# ST_LINK_V2-1.net
KiCad netlist of a schematic drawn in Altium Designer
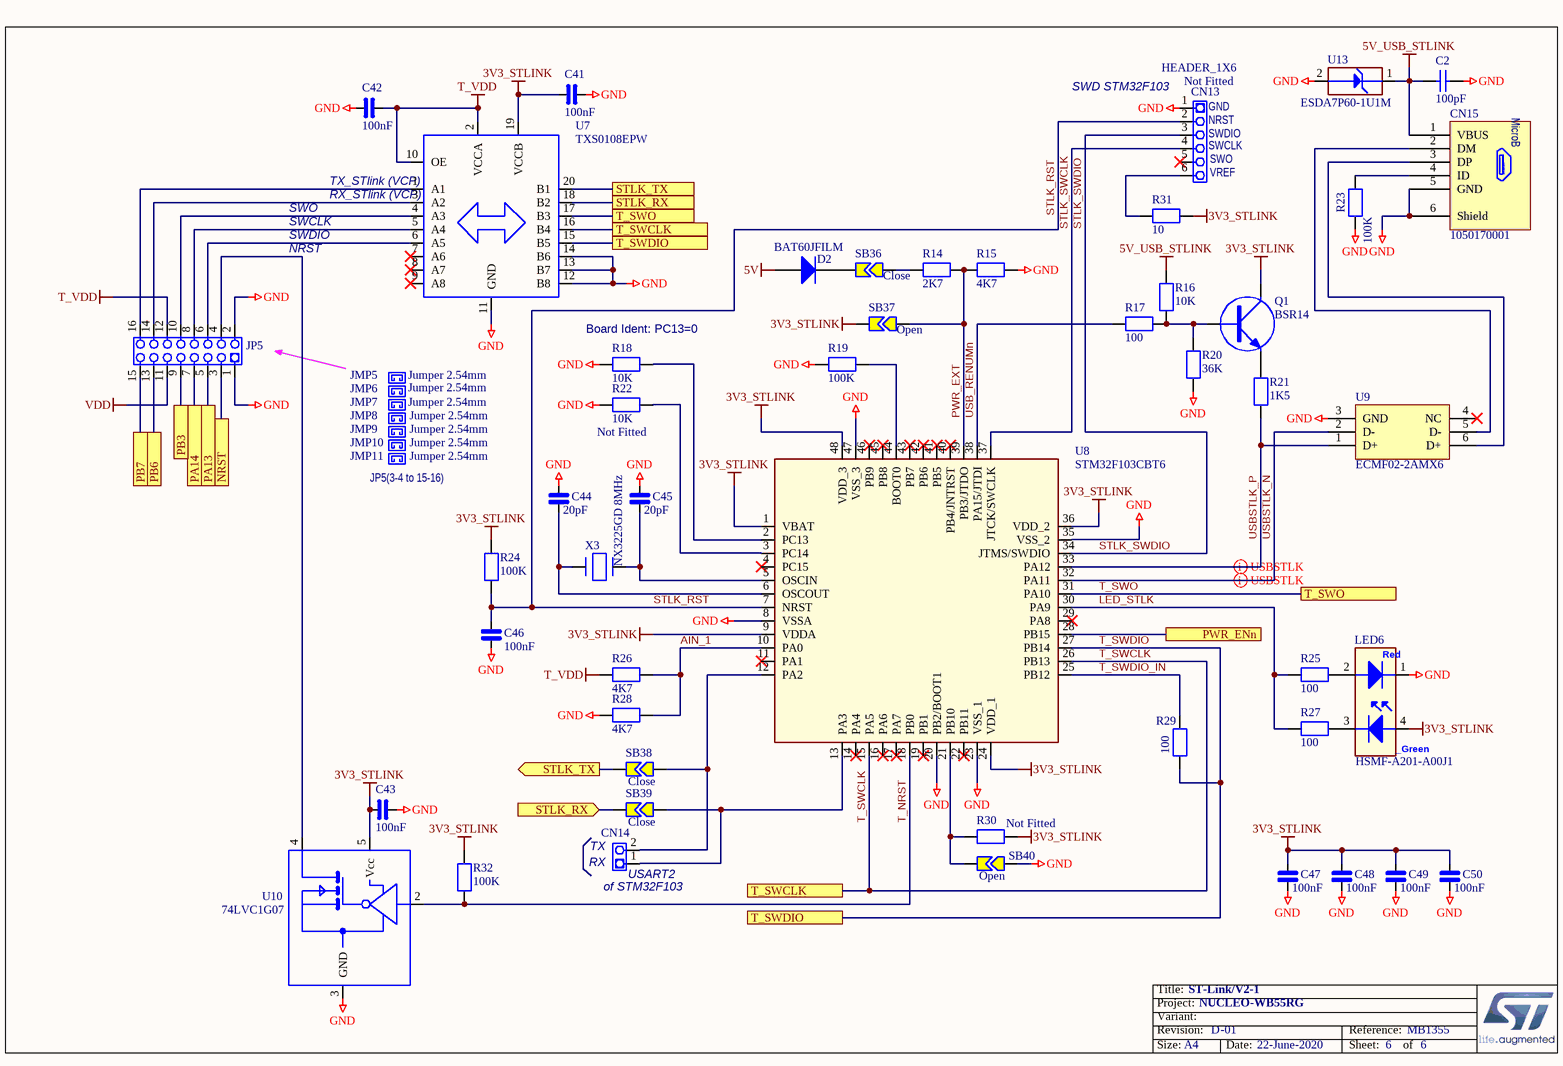
[diagram p0: ST_LINK_V2-1.SCHDOC]

(export (version "E")
  (design (tool "Eeschema 10.0.6"))
  (components
    (comp (ref "C2")
      (value "100pF")
      (footprint "C0402")
      (description "Capacitor, MLCC, 100pF, 50V, NPO, 5%, 0402, T=0,5mm")
      (fields
        (field (name "INTERNAL_PART_NUMBER") "MCD-00205")
        (field (name "MANUFACTURER_PART_NUMBER") "CC0402JRNPO9BN101")
        (field (name "PROVIDED_BY") "SUBCO")
      )
      (libsource (lib "MCD_PARTS_database") (part "Capacitor"))
    )
    (comp (ref "C41")
      (value "100nF")
      (footprint "0402_CAP_NPOL")
      (description "Capacitor_not polarized")
      (libsource (lib "ST_Lib3D") (part "CAP_NPOL"))
    )
    (comp (ref "C42")
      (value "100nF")
      (footprint "0402_CAP_NPOL")
      (description "Capacitor_not polarized")
      (libsource (lib "ST_Lib3D") (part "CAP_NPOL"))
    )
    (comp (ref "C43")
      (value "100nF")
      (footprint "0402_CAP_NPOL")
      (description "Capacitor_not polarized")
      (libsource (lib "ST_Lib3D") (part "CAP_NPOL"))
    )
    (comp (ref "C44")
      (value "20pF")
      (footprint "0402_CAP_NPOL")
      (description "Capacitor_not polarized")
      (libsource (lib "ST_Lib3D") (part "CAP_NPOL"))
    )
    (comp (ref "C45")
      (value "20pF")
      (footprint "0402_CAP_NPOL")
      (description "Capacitor_not polarized")
      (libsource (lib "ST_Lib3D") (part "CAP_NPOL"))
    )
    (comp (ref "C46")
      (value "100nF")
      (footprint "0402_CAP_NPOL")
      (description "Capacitor_not polarized")
      (libsource (lib "ST_Lib3D") (part "CAP_NPOL"))
    )
    (comp (ref "C47")
      (value "100nF")
      (footprint "0402_CAP_NPOL")
      (description "Capacitor_not polarized")
      (libsource (lib "ST_Lib3D") (part "CAP_NPOL"))
    )
    (comp (ref "C48")
      (value "100nF")
      (footprint "0402_CAP_NPOL")
      (description "Capacitor_not polarized")
      (libsource (lib "ST_Lib3D") (part "CAP_NPOL"))
    )
    (comp (ref "C49")
      (value "100nF")
      (footprint "0402_CAP_NPOL")
      (description "Capacitor_not polarized")
      (libsource (lib "ST_Lib3D") (part "CAP_NPOL"))
    )
    (comp (ref "C50")
      (value "100nF")
      (footprint "0402_CAP_NPOL")
      (description "Capacitor_not polarized")
      (libsource (lib "ST_Lib3D") (part "CAP_NPOL"))
    )
    (comp (ref "CN13")
      (value "HEADER_1X6")
      (footprint "Header NF 1x6x2.54 TH")
      (fields (field (name "FITTED") "Not Fitted"))
      (libsource (lib "Connector") (part "HEADER_1X6"))
    )
    (comp (ref "CN14")
      (value "HEADER_1X2")
      (footprint "Header NF 1x2x2.54 TH")
      (libsource (lib "Connector") (part "HEADER_1X2"))
    )
    (comp (ref "CN15")
      (value "1050170001")
      (footprint "USBMICROB_MOLEX_105017-0001_H2P90")
      (description "USB-MICRO-B, 1050170001, SMT, MOLEX")
      (libsource (lib "Connector") (part "1050170001"))
    )
    (comp (ref "D2")
      (value "BAT60JFILM")
      (footprint "SOD-323")
      (description "Default Diode")
      (fields (field (name "PUBLISHER") "Altium Limited"))
      (libsource (lib "MB1144_1") (part "Diode"))
    )
    (comp (ref "JMP5")
      (value "Jumper 2.54mm")
      (footprint "Jumper 2.54mm BLACK")
      (libsource (lib "Connector") (part "Jumper 2.54mm"))
    )
    (comp (ref "JMP6")
      (value "Jumper 2.54mm")
      (footprint "Jumper 2.54mm BLACK")
      (libsource (lib "Connector") (part "Jumper 2.54mm"))
    )
    (comp (ref "JMP7")
      (value "Jumper 2.54mm")
      (footprint "Jumper 2.54mm BLACK")
      (libsource (lib "Connector") (part "Jumper 2.54mm"))
    )
    (comp (ref "JMP8")
      (value "Jumper 2.54mm")
      (footprint "Jumper 2.54mm BLACK")
      (libsource (lib "Connector") (part "Jumper 2.54mm"))
    )
    (comp (ref "JMP9")
      (value "Jumper 2.54mm")
      (footprint "Jumper 2.54mm BLACK")
      (libsource (lib "Connector") (part "Jumper 2.54mm"))
    )
    (comp (ref "JMP10")
      (value "Jumper 2.54mm")
      (footprint "Jumper 2.54mm BLACK")
      (libsource (lib "Connector") (part "Jumper 2.54mm"))
    )
    (comp (ref "JMP11")
      (value "Jumper 2.54mm")
      (footprint "Jumper 2.54mm BLACK")
      (libsource (lib "Connector") (part "Jumper 2.54mm"))
    )
    (comp (ref "JP5")
      (value "HEADER_2X8")
      (footprint "Header M 2x8x2.54 TH V")
      (libsource (lib "Connector") (part "HEADER_2X8"))
    )
    (comp (ref "LED6")
      (value "HSMF-A201-A00J1")
      (footprint "HSMF-A201")
      (description "Bicolor Led")
      (libsource (lib "MB1136") (part "LD_BICOLOR_CMS"))
    )
    (comp (ref "Q1")
      (value "BSR14")
      (footprint "SOT23-3")
      (description "2N2222_SOT23")
      (libsource (lib "Active") (part "2N2222"))
    )
    (comp (ref "R14")
      (value "2K7")
      (footprint "0402_RES")
      (description "Resistor")
      (libsource (lib "Lib3D_Altium10_Schlib") (part "RES"))
    )
    (comp (ref "R15")
      (value "4K7")
      (footprint "0402_RES")
      (description "Resistor")
      (libsource (lib "Lib3D_Altium10_Schlib") (part "RES"))
    )
    (comp (ref "R16")
      (value "10K")
      (footprint "0402_RES")
      (description "Resistor")
      (libsource (lib "Lib3D_Altium10_Schlib") (part "RES"))
    )
    (comp (ref "R17")
      (value "100")
      (footprint "0402_RES")
      (description "Resistor")
      (libsource (lib "Lib3D_Altium10_Schlib") (part "RES"))
    )
    (comp (ref "R18")
      (value "10K")
      (footprint "0402_RES")
      (description "Resistor")
      (libsource (lib "Lib3D_Altium10_Schlib") (part "RES"))
    )
    (comp (ref "R19")
      (value "100K")
      (footprint "0402_RES")
      (description "Resistor")
      (libsource (lib "Lib3D_Altium10_Schlib") (part "RES"))
    )
    (comp (ref "R20")
      (value "36K")
      (footprint "0402_RES")
      (description "Resistor")
      (libsource (lib "Lib3D_Altium10_Schlib") (part "RES"))
    )
    (comp (ref "R21")
      (value "1K5")
      (footprint "0402_RES")
      (description "Resistor")
      (libsource (lib "Lib3D_Altium10_Schlib") (part "RES"))
    )
    (comp (ref "R22")
      (value "10K")
      (footprint "0402_RES")
      (description "Resistor")
      (fields (field (name "FITTED") "Not Fitted"))
      (libsource (lib "Lib3D_Altium10_Schlib") (part "RES"))
    )
    (comp (ref "R23")
      (value "100K")
      (footprint "0402_RES")
      (description "Resistor")
      (libsource (lib "Lib3D_Altium10_Schlib") (part "RES"))
    )
    (comp (ref "R24")
      (value "100K")
      (footprint "0402_RES")
      (description "Resistor")
      (libsource (lib "Lib3D_Altium10_Schlib") (part "RES"))
    )
    (comp (ref "R25")
      (value "100")
      (footprint "0402_RES")
      (description "Resistor")
      (libsource (lib "Lib3D_Altium10_Schlib") (part "RES"))
    )
    (comp (ref "R26")
      (value "4K7")
      (footprint "0402_RES")
      (description "Resistor")
      (libsource (lib "Lib3D_Altium10_Schlib") (part "RES"))
    )
    (comp (ref "R27")
      (value "100")
      (footprint "0402_RES")
      (description "Resistor")
      (libsource (lib "Lib3D_Altium10_Schlib") (part "RES"))
    )
    (comp (ref "R28")
      (value "4K7")
      (footprint "0402_RES")
      (description "Resistor")
      (libsource (lib "Lib3D_Altium10_Schlib") (part "RES"))
    )
    (comp (ref "R29")
      (value "100")
      (footprint "0402_RES")
      (description "Resistor")
      (libsource (lib "Lib3D_Altium10_Schlib") (part "RES"))
    )
    (comp (ref "R30")
      (value "~")
      (footprint "0402_RES")
      (description "Resistor")
      (fields (field (name "FITTED") "Not Fitted"))
      (libsource (lib "Lib3D_Altium10_Schlib") (part "RES"))
    )
    (comp (ref "R31")
      (value "10")
      (footprint "0402_RES")
      (description "Resistor")
      (libsource (lib "Lib3D_Altium10_Schlib") (part "RES"))
    )
    (comp (ref "R32")
      (value "100K")
      (footprint "0402_RES")
      (description "Resistor")
      (libsource (lib "Lib3D_Altium10_Schlib") (part "RES"))
    )
    (comp (ref "SB36")
      (value "Close")
      (footprint "SB-tiny")
      (description "Solder Jumper")
      (fields (field (name "PUBLISHER") "Altium Limited"))
      (libsource (lib "Lib3D_Altium10_Schlib") (part "Strap2"))
    )
    (comp (ref "SB37")
      (value "Open")
      (footprint "SB-tiny")
      (description "Solder Jumper")
      (fields (field (name "PUBLISHER") "Altium Limited"))
      (libsource (lib "Lib3D_Altium10_Schlib") (part "Strap2"))
    )
    (comp (ref "SB38")
      (value "Close")
      (footprint "SB-tiny")
      (description "Solder Jumper")
      (fields (field (name "PUBLISHER") "Altium Limited"))
      (libsource (lib "Lib3D_Altium10_Schlib") (part "Strap2"))
    )
    (comp (ref "SB39")
      (value "Close")
      (footprint "SB-tiny")
      (description "Solder Jumper")
      (fields (field (name "PUBLISHER") "Altium Limited"))
      (libsource (lib "Lib3D_Altium10_Schlib") (part "Strap2"))
    )
    (comp (ref "SB40")
      (value "Open")
      (footprint "SB-tiny")
      (description "Solder Jumper")
      (fields (field (name "PUBLISHER") "Altium Limited"))
      (libsource (lib "Lib3D_Altium10_Schlib") (part "Strap2"))
    )
    (comp (ref "U7")
      (value "TXS0108EPW")
      (footprint "TSSOP20")
      (description "TXS0108E Bi-directional Level Shifter TSSOP20")
      (libsource (lib "Active") (part "TXS0108EPW"))
    )
    (comp (ref "U8")
      (value "STM32F103CBT6")
      (footprint "LQFP48_7X7_P050")
      (description "Medium-density performance line ARM-based 32-bit MCU with 128KB Flash")
      (libsource (lib "Active") (part "STM32F103CBT6"))
    )
    (comp (ref "U9")
      (value "ECMF02-2AMX6")
      (footprint "ESD_QFN-6L_1P7X1P5_P050")
      (description "Common mode filter with ESD protection for USB 2.0 interface")
      (fields
        (field (name "INTERNAL_PART_NUMBER") "MCD-00649")
        (field (name "MANUFACTURER") "STMICROELECTRONICS")
        (field (name "PROVIDED_BY") "SUBCO with ST control")
      )
      (libsource (lib "MCD_PARTS_database") (part "ECMF02-2AMX6"))
    )
    (comp (ref "U10")
      (value "74LVC1G07")
      (footprint "SOT353-1")
      (libsource (lib "ST_Lib3D") (part "74LVC1G07"))
    )
    (comp (ref "U13")
      (value "ESDA7P60-1U1M")
      (footprint "ESD_QFN2_1P6X1_P125")
      (description "High power transient voltage suppressor, 7V breakdown")
      (fields
        (field (name "INTERNAL_PART_NUMBER") "MCD-00251")
        (field (name "MANUFACTURER") "STMICROELECTRONICS")
        (field (name "PROVIDED_BY") "SUBCO with ST control")
      )
      (libsource (lib "MCD_PARTS_database") (part "ESD-TRANSIL"))
    )
    (comp (ref "X3")
      (value "NX3225GD 8MHz")
      (footprint "CRY_NX3225GD_2P")
      (description "Crystal 8MHz, 8pF, +-20ppm, 500ohms max,  SMD")
      (fields
        (field (name "INTERNAL_PART_NUMBER") "MCD-00092")
        (field (name "MANUFACTURER_PART_NUMBER") "NX3225GD 8MHz EXS00A-CG04874")
        (field (name "PROVIDED_BY") "SUBCO")
      )
      (libsource (lib "MCD_PARTS_database") (part "XTAL_2_PINS"))
    )
  )
  (nets
    (net (code "1") (name "/AIN_1") (class "Default")
      (node (ref "R26") (pin "1") (pinfunction "1_1") (pintype "passive"))
      (node (ref "R28") (pin "1") (pinfunction "1_1") (pintype "passive"))
      (node (ref "U8") (pin "10") (pinfunction "PA0_10") (pintype "passive"))
    )
    (net (code "2") (name "/LED_STLK") (class "Default")
      (node (ref "R25") (pin "2") (pinfunction "2_2") (pintype "passive"))
      (node (ref "R27") (pin "2") (pinfunction "2_2") (pintype "passive"))
      (node (ref "U8") (pin "30") (pinfunction "PA9_30") (pintype "passive"))
    )
    (net (code "3") (name "/NRST") (class "Default")
      (node (ref "JP5") (pin "3") (pinfunction "3_3") (pintype "passive"))
    )
    (net (code "4") (name "/PA13") (class "Default")
      (node (ref "JP5") (pin "5") (pinfunction "5_5") (pintype "passive"))
    )
    (net (code "5") (name "/PA14") (class "Default")
      (node (ref "JP5") (pin "7") (pinfunction "7_7") (pintype "passive"))
    )
    (net (code "6") (name "/PB3") (class "Default")
      (node (ref "JP5") (pin "9") (pinfunction "9_9") (pintype "passive"))
    )
    (net (code "7") (name "/PB6") (class "Default")
      (node (ref "JP5") (pin "13") (pinfunction "13_13") (pintype "passive"))
    )
    (net (code "8") (name "/PB7") (class "Default")
      (node (ref "JP5") (pin "15") (pinfunction "15_15") (pintype "passive"))
    )
    (net (code "9") (name "/PWR_ENn") (class "Default")
      (node (ref "U8") (pin "28") (pinfunction "PB15_28") (pintype "passive"))
    )
    (net (code "10") (name "/PWR_EXT") (class "Default")
      (node (ref "R14") (pin "2") (pinfunction "2_2") (pintype "passive"))
      (node (ref "R15") (pin "1") (pinfunction "1_1") (pintype "passive"))
      (node (ref "SB37") (pin "2") (pinfunction "2_2") (pintype "passive"))
      (node (ref "U8") (pin "39") (pinfunction "PB3/JTDO_39") (pintype "passive"))
    )
    (net (code "11") (name "/STLK_RST") (class "Default")
      (node (ref "C46") (pin "2") (pinfunction "2_2") (pintype "passive"))
      (node (ref "CN13") (pin "2") (pinfunction "2_2") (pintype "passive"))
      (node (ref "R24") (pin "1") (pinfunction "1_1") (pintype "passive"))
      (node (ref "U8") (pin "7") (pinfunction "NRST_7") (pintype "passive"))
    )
    (net (code "12") (name "/STLK_RX") (class "Default")
      (node (ref "SB39") (pin "1") (pinfunction "1_1") (pintype "passive"))
      (node (ref "U7") (pin "18") (pinfunction "B2_18") (pintype "passive"))
    )
    (net (code "13") (name "/STLK_SWCLK") (class "Default")
      (node (ref "CN13") (pin "4") (pinfunction "4_4") (pintype "passive"))
      (node (ref "U8") (pin "37") (pinfunction "JTCK/SWCLK_37") (pintype "passive"))
    )
    (net (code "14") (name "/STLK_SWDIO") (class "Default")
      (node (ref "CN13") (pin "3") (pinfunction "3_3") (pintype "passive"))
      (node (ref "U8") (pin "34") (pinfunction "JTMS/SWDIO_34") (pintype "passive"))
    )
    (net (code "15") (name "/STLK_TX") (class "Default")
      (node (ref "SB38") (pin "1") (pinfunction "1_1") (pintype "passive"))
      (node (ref "U7") (pin "20") (pinfunction "B1_20") (pintype "passive"))
    )
    (net (code "16") (name "/T_NRST") (class "Default")
      (node (ref "R32") (pin "1") (pinfunction "1_1") (pintype "passive"))
      (node (ref "U10") (pin "2") (pinfunction "A_2") (pintype "passive"))
      (node (ref "U8") (pin "18") (pinfunction "PB0_18") (pintype "passive"))
    )
    (net (code "17") (name "/T_SWCLK") (class "Default")
      (node (ref "U7") (pin "16") (pinfunction "B4_16") (pintype "passive"))
      (node (ref "U8") (pin "15") (pinfunction "PA5_15") (pintype "passive"))
      (node (ref "U8") (pin "26") (pinfunction "PB13_26") (pintype "passive"))
    )
    (net (code "18") (name "/T_SWDIO") (class "Default")
      (node (ref "R29") (pin "1") (pinfunction "1_1") (pintype "passive"))
      (node (ref "U7") (pin "15") (pinfunction "B5_15") (pintype "passive"))
      (node (ref "U8") (pin "27") (pinfunction "PB14_27") (pintype "passive"))
    )
    (net (code "19") (name "/T_SWDIO_IN") (class "Default")
      (node (ref "R29") (pin "2") (pinfunction "2_2") (pintype "passive"))
      (node (ref "U8") (pin "25") (pinfunction "PB12_25") (pintype "passive"))
    )
    (net (code "20") (name "/T_SWO") (class "Default")
      (node (ref "U7") (pin "17") (pinfunction "B3_17") (pintype "passive"))
      (node (ref "U8") (pin "31") (pinfunction "PA10_31") (pintype "passive"))
    )
    (net (code "21") (name "/USBSTLK_N") (class "Default")
      (node (ref "U8") (pin "32") (pinfunction "PA11_32") (pintype "passive"))
      (node (ref "U9") (pin "2") (pinfunction "D-_2") (pintype "passive"))
    )
    (net (code "22") (name "/USBSTLK_P") (class "Default")
      (node (ref "R21") (pin "1") (pinfunction "1_1") (pintype "passive"))
      (node (ref "U8") (pin "33") (pinfunction "PA12_33") (pintype "passive"))
      (node (ref "U9") (pin "1") (pinfunction "D+_1") (pintype "passive"))
    )
    (net (code "23") (name "/USB_RENUMn") (class "Default")
      (node (ref "R17") (pin "2") (pinfunction "2_2") (pintype "passive"))
      (node (ref "U8") (pin "38") (pinfunction "PA15/JTDI_38") (pintype "passive"))
    )
    (net (code "24") (name "3V3_STLINK") (class "Default")
      (node (ref "C41") (pin "1") (pinfunction "1_1") (pintype "passive"))
      (node (ref "C43") (pin "1") (pinfunction "1_1") (pintype "passive"))
      (node (ref "C47") (pin "1") (pinfunction "1_1") (pintype "passive"))
      (node (ref "C48") (pin "1") (pinfunction "1_1") (pintype "passive"))
      (node (ref "C49") (pin "1") (pinfunction "1_1") (pintype "passive"))
      (node (ref "C50") (pin "1") (pinfunction "1_1") (pintype "passive"))
      (node (ref "LED6") (pin "4") (pinfunction "4_4") (pintype "passive"))
      (node (ref "Q1") (pin "3") (pinfunction "C_3") (pintype "passive"))
      (node (ref "R24") (pin "2") (pinfunction "2_2") (pintype "passive"))
      (node (ref "R30") (pin "1") (pinfunction "1_1") (pintype "passive"))
      (node (ref "R31") (pin "2") (pinfunction "2_2") (pintype "passive"))
      (node (ref "R32") (pin "2") (pinfunction "2_2") (pintype "passive"))
      (node (ref "SB37") (pin "1") (pinfunction "1_1") (pintype "passive"))
      (node (ref "U10") (pin "5") (pinfunction "Vcc_5") (pintype "passive"))
      (node (ref "U7") (pin "19") (pinfunction "VCCB_19") (pintype "passive"))
      (node (ref "U8") (pin "1") (pinfunction "VBAT_1") (pintype "passive"))
      (node (ref "U8") (pin "24") (pinfunction "VDD_1_24") (pintype "passive"))
      (node (ref "U8") (pin "36") (pinfunction "VDD_2_36") (pintype "passive"))
      (node (ref "U8") (pin "48") (pinfunction "VDD_3_48") (pintype "passive"))
      (node (ref "U8") (pin "9") (pinfunction "VDDA_9") (pintype "passive"))
    )
    (net (code "25") (name "5V") (class "Default")
      (node (ref "D2") (pin "1") (pinfunction "A_1") (pintype "passive"))
    )
    (net (code "26") (name "5V_USB_STLINK") (class "Default")
      (node (ref "C2") (pin "1") (pinfunction "1_1") (pintype "passive"))
      (node (ref "CN15") (pin "1") (pinfunction "VBUS_1") (pintype "passive"))
      (node (ref "R16") (pin "2") (pinfunction "2_2") (pintype "passive"))
      (node (ref "U13") (pin "1") (pinfunction "IO1_1") (pintype "passive"))
    )
    (net (code "27") (name "GND") (class "Default")
      (node (ref "C2") (pin "2") (pinfunction "2_2") (pintype "passive"))
      (node (ref "C41") (pin "2") (pinfunction "2_2") (pintype "passive"))
      (node (ref "C42") (pin "1") (pinfunction "1_1") (pintype "passive"))
      (node (ref "C43") (pin "2") (pinfunction "2_2") (pintype "passive"))
      (node (ref "C44") (pin "1") (pinfunction "1_1") (pintype "passive"))
      (node (ref "C45") (pin "1") (pinfunction "1_1") (pintype "passive"))
      (node (ref "C46") (pin "1") (pinfunction "1_1") (pintype "passive"))
      (node (ref "C47") (pin "2") (pinfunction "2_2") (pintype "passive"))
      (node (ref "C48") (pin "2") (pinfunction "2_2") (pintype "passive"))
      (node (ref "C49") (pin "2") (pinfunction "2_2") (pintype "passive"))
      (node (ref "C50") (pin "2") (pinfunction "2_2") (pintype "passive"))
      (node (ref "CN13") (pin "1") (pinfunction "1_1") (pintype "passive"))
      (node (ref "CN15") (pin "5") (pinfunction "GND_5") (pintype "passive"))
      (node (ref "CN15") (pin "6") (pinfunction "Shield_6") (pintype "passive"))
      (node (ref "JP5") (pin "1") (pinfunction "1_1") (pintype "passive"))
      (node (ref "JP5") (pin "2") (pinfunction "2_2") (pintype "passive"))
      (node (ref "LED6") (pin "1") (pinfunction "1_1") (pintype "passive"))
      (node (ref "R15") (pin "2") (pinfunction "2_2") (pintype "passive"))
      (node (ref "R18") (pin "2") (pinfunction "2_2") (pintype "passive"))
      (node (ref "R19") (pin "1") (pinfunction "1_1") (pintype "passive"))
      (node (ref "R20") (pin "1") (pinfunction "1_1") (pintype "passive"))
      (node (ref "R22") (pin "2") (pinfunction "2_2") (pintype "passive"))
      (node (ref "R23") (pin "1") (pinfunction "1_1") (pintype "passive"))
      (node (ref "R28") (pin "2") (pinfunction "2_2") (pintype "passive"))
      (node (ref "SB40") (pin "2") (pinfunction "2_2") (pintype "passive"))
      (node (ref "U10") (pin "3") (pinfunction "GND_3") (pintype "passive"))
      (node (ref "U13") (pin "2") (pinfunction "GND_2") (pintype "passive"))
      (node (ref "U7") (pin "11") (pinfunction "GND_11") (pintype "passive"))
      (node (ref "U7") (pin "12") (pinfunction "B8_12") (pintype "passive"))
      (node (ref "U7") (pin "13") (pinfunction "B7_13") (pintype "passive"))
      (node (ref "U7") (pin "14") (pinfunction "B6_14") (pintype "passive"))
      (node (ref "U8") (pin "20") (pinfunction "PB2/BOOT1_20") (pintype "passive"))
      (node (ref "U8") (pin "23") (pinfunction "VSS_1_23") (pintype "passive"))
      (node (ref "U8") (pin "35") (pinfunction "VSS_2_35") (pintype "passive"))
      (node (ref "U8") (pin "47") (pinfunction "VSS_3_47") (pintype "passive"))
      (node (ref "U8") (pin "8") (pinfunction "VSSA_8") (pintype "passive"))
      (node (ref "U9") (pin "3") (pinfunction "GND_3") (pintype "passive"))
    )
    (net (code "28") (name "Net-(CN13-Pad6)") (class "Default")
      (node (ref "CN13") (pin "6") (pinfunction "6_6") (pintype "passive"))
      (node (ref "R31") (pin "1") (pinfunction "1_1") (pintype "passive"))
    )
    (net (code "29") (name "Net-(CN15-DM)") (class "Default")
      (node (ref "CN15") (pin "2") (pinfunction "DM_2") (pintype "passive"))
      (node (ref "U9") (pin "5") (pinfunction "D-_5") (pintype "passive"))
    )
    (net (code "30") (name "Net-(CN15-DP)") (class "Default")
      (node (ref "CN15") (pin "3") (pinfunction "DP_3") (pintype "passive"))
      (node (ref "U9") (pin "6") (pinfunction "D+_6") (pintype "passive"))
    )
    (net (code "31") (name "Net-(CN15-ID)") (class "Default")
      (node (ref "CN15") (pin "4") (pinfunction "ID_4") (pintype "passive"))
      (node (ref "R23") (pin "2") (pinfunction "2_2") (pintype "passive"))
    )
    (net (code "32") (name "Net-(D2-K)") (class "Default")
      (node (ref "D2") (pin "2") (pinfunction "K_2") (pintype "passive"))
      (node (ref "SB36") (pin "1") (pinfunction "1_1") (pintype "passive"))
    )
    (net (code "33") (name "Net-(LED6-Pad2)") (class "Default")
      (node (ref "LED6") (pin "2") (pinfunction "2_2") (pintype "passive"))
      (node (ref "R25") (pin "1") (pinfunction "1_1") (pintype "passive"))
    )
    (net (code "34") (name "Net-(LED6-Pad3)") (class "Default")
      (node (ref "LED6") (pin "3") (pinfunction "3_3") (pintype "passive"))
      (node (ref "R27") (pin "1") (pinfunction "1_1") (pintype "passive"))
    )
    (net (code "35") (name "Net-(Q1-B)") (class "Default")
      (node (ref "Q1") (pin "1") (pinfunction "B_1") (pintype "passive"))
      (node (ref "R16") (pin "1") (pinfunction "1_1") (pintype "passive"))
      (node (ref "R17") (pin "1") (pinfunction "1_1") (pintype "passive"))
      (node (ref "R20") (pin "2") (pinfunction "2_2") (pintype "passive"))
    )
    (net (code "36") (name "Net-(Q1-E)") (class "Default")
      (node (ref "Q1") (pin "2") (pinfunction "E_2") (pintype "passive"))
      (node (ref "R21") (pin "2") (pinfunction "2_2") (pintype "passive"))
    )
    (net (code "37") (name "Net-(R14-Pad1)") (class "Default")
      (node (ref "R14") (pin "1") (pinfunction "1_1") (pintype "passive"))
      (node (ref "SB36") (pin "2") (pinfunction "2_2") (pintype "passive"))
    )
    (net (code "38") (name "Net-(U7-A1)") (class "Default")
      (node (ref "JP5") (pin "16") (pinfunction "16_16") (pintype "passive"))
      (node (ref "U7") (pin "1") (pinfunction "A1_1") (pintype "passive"))
    )
    (net (code "39") (name "Net-(U7-A2)") (class "Default")
      (node (ref "JP5") (pin "14") (pinfunction "14_14") (pintype "passive"))
      (node (ref "U7") (pin "3") (pinfunction "A2_3") (pintype "passive"))
    )
    (net (code "40") (name "Net-(U7-A3)") (class "Default")
      (node (ref "JP5") (pin "10") (pinfunction "10_10") (pintype "passive"))
      (node (ref "U7") (pin "4") (pinfunction "A3_4") (pintype "passive"))
    )
    (net (code "41") (name "Net-(U7-A4)") (class "Default")
      (node (ref "JP5") (pin "8") (pinfunction "8_8") (pintype "passive"))
      (node (ref "U7") (pin "5") (pinfunction "A4_5") (pintype "passive"))
    )
    (net (code "42") (name "Net-(U7-A5)") (class "Default")
      (node (ref "JP5") (pin "6") (pinfunction "6_6") (pintype "passive"))
      (node (ref "U7") (pin "6") (pinfunction "A5_6") (pintype "passive"))
    )
    (net (code "43") (name "Net-(U8-BOOT0)") (class "Default")
      (node (ref "R19") (pin "2") (pinfunction "2_2") (pintype "passive"))
      (node (ref "U8") (pin "44") (pinfunction "BOOT0_44") (pintype "passive"))
    )
    (net (code "44") (name "Net-(U8-OSCIN)") (class "Default")
      (node (ref "C45") (pin "2") (pinfunction "2_2") (pintype "passive"))
      (node (ref "U8") (pin "5") (pinfunction "OSCIN_5") (pintype "passive"))
      (node (ref "X3") (pin "1") (pinfunction "X1_1") (pintype "passive"))
    )
    (net (code "45") (name "Net-(U8-OSCOUT)") (class "Default")
      (node (ref "C44") (pin "2") (pinfunction "2_2") (pintype "passive"))
      (node (ref "U8") (pin "6") (pinfunction "OSCOUT_6") (pintype "passive"))
      (node (ref "X3") (pin "2") (pinfunction "X2_2") (pintype "passive"))
    )
    (net (code "46") (name "Net-(U8-PA2)") (class "Default")
      (node (ref "CN14") (pin "2") (pinfunction "2_2") (pintype "passive"))
      (node (ref "SB38") (pin "2") (pinfunction "2_2") (pintype "passive"))
      (node (ref "U8") (pin "12") (pinfunction "PA2_12") (pintype "passive"))
    )
    (net (code "47") (name "Net-(U8-PA3)") (class "Default")
      (node (ref "CN14") (pin "1") (pinfunction "1_1") (pintype "passive"))
      (node (ref "SB39") (pin "2") (pinfunction "2_2") (pintype "passive"))
      (node (ref "U8") (pin "13") (pinfunction "PA3_13") (pintype "passive"))
    )
    (net (code "48") (name "Net-(U8-PB10)") (class "Default")
      (node (ref "R30") (pin "2") (pinfunction "2_2") (pintype "passive"))
      (node (ref "SB40") (pin "1") (pinfunction "1_1") (pintype "passive"))
      (node (ref "U8") (pin "21") (pinfunction "PB10_21") (pintype "passive"))
    )
    (net (code "49") (name "Net-(U8-PC13)") (class "Default")
      (node (ref "R18") (pin "1") (pinfunction "1_1") (pintype "passive"))
      (node (ref "U8") (pin "2") (pinfunction "PC13_2") (pintype "passive"))
    )
    (net (code "50") (name "Net-(U8-PC14)") (class "Default")
      (node (ref "R22") (pin "1") (pinfunction "1_1") (pintype "passive"))
      (node (ref "U8") (pin "3") (pinfunction "PC14_3") (pintype "passive"))
    )
    (net (code "51") (name "Net-(U10-Y)") (class "Default")
      (node (ref "JP5") (pin "4") (pinfunction "4_4") (pintype "passive"))
      (node (ref "U10") (pin "4") (pinfunction "Y_4") (pintype "passive"))
    )
    (net (code "52") (name "T_VDD") (class "Default")
      (node (ref "C42") (pin "2") (pinfunction "2_2") (pintype "passive"))
      (node (ref "JP5") (pin "12") (pinfunction "12_12") (pintype "passive"))
      (node (ref "R26") (pin "2") (pinfunction "2_2") (pintype "passive"))
      (node (ref "U7") (pin "10") (pinfunction "OE_10") (pintype "passive"))
      (node (ref "U7") (pin "2") (pinfunction "VCCA_2") (pintype "passive"))
    )
    (net (code "53") (name "VDD") (class "Default")
      (node (ref "JP5") (pin "11") (pinfunction "11_11") (pintype "passive"))
    )
    (net (code "54") (name "unconnected-(CN13-Pad5)") (class "Default")
      (node (ref "CN13") (pin "5") (pinfunction "5_5") (pintype "passive+no_connect"))
    )
    (net (code "55") (name "unconnected-(U7-A6-Pad7)") (class "Default")
      (node (ref "U7") (pin "7") (pinfunction "A6_7") (pintype "passive+no_connect"))
    )
    (net (code "56") (name "unconnected-(U7-A7-Pad8)") (class "Default")
      (node (ref "U7") (pin "8") (pinfunction "A7_8") (pintype "passive+no_connect"))
    )
    (net (code "57") (name "unconnected-(U7-A8-Pad9)") (class "Default")
      (node (ref "U7") (pin "9") (pinfunction "A8_9") (pintype "passive+no_connect"))
    )
    (net (code "58") (name "unconnected-(U8-PA1-Pad11)") (class "Default")
      (node (ref "U8") (pin "11") (pinfunction "PA1_11") (pintype "passive+no_connect"))
    )
    (net (code "59") (name "unconnected-(U8-PA4-Pad14)") (class "Default")
      (node (ref "U8") (pin "14") (pinfunction "PA4_14") (pintype "passive+no_connect"))
    )
    (net (code "60") (name "unconnected-(U8-PA6-Pad16)") (class "Default")
      (node (ref "U8") (pin "16") (pinfunction "PA6_16") (pintype "passive+no_connect"))
    )
    (net (code "61") (name "unconnected-(U8-PA7-Pad17)") (class "Default")
      (node (ref "U8") (pin "17") (pinfunction "PA7_17") (pintype "passive+no_connect"))
    )
    (net (code "62") (name "unconnected-(U8-PA8-Pad29)") (class "Default")
      (node (ref "U8") (pin "29") (pinfunction "PA8_29") (pintype "passive+no_connect"))
    )
    (net (code "63") (name "unconnected-(U8-PB1-Pad19)") (class "Default")
      (node (ref "U8") (pin "19") (pinfunction "PB1_19") (pintype "passive+no_connect"))
    )
    (net (code "64") (name "unconnected-(U8-PB4{slash}JNTRST-Pad40)") (class "Default")
      (node (ref "U8") (pin "40") (pinfunction "PB4/JNTRST_40") (pintype "passive+no_connect"))
    )
    (net (code "65") (name "unconnected-(U8-PB5-Pad41)") (class "Default")
      (node (ref "U8") (pin "41") (pinfunction "PB5_41") (pintype "passive+no_connect"))
    )
    (net (code "66") (name "unconnected-(U8-PB6-Pad42)") (class "Default")
      (node (ref "U8") (pin "42") (pinfunction "PB6_42") (pintype "passive+no_connect"))
    )
    (net (code "67") (name "unconnected-(U8-PB7-Pad43)") (class "Default")
      (node (ref "U8") (pin "43") (pinfunction "PB7_43") (pintype "passive+no_connect"))
    )
    (net (code "68") (name "unconnected-(U8-PB8-Pad45)") (class "Default")
      (node (ref "U8") (pin "45") (pinfunction "PB8_45") (pintype "passive+no_connect"))
    )
    (net (code "69") (name "unconnected-(U8-PB9-Pad46)") (class "Default")
      (node (ref "U8") (pin "46") (pinfunction "PB9_46") (pintype "passive+no_connect"))
    )
    (net (code "70") (name "unconnected-(U8-PB11-Pad22)") (class "Default")
      (node (ref "U8") (pin "22") (pinfunction "PB11_22") (pintype "passive+no_connect"))
    )
    (net (code "71") (name "unconnected-(U8-PC15-Pad4)") (class "Default")
      (node (ref "U8") (pin "4") (pinfunction "PC15_4") (pintype "passive+no_connect"))
    )
    (net (code "72") (name "unconnected-(U9-NC-Pad4)") (class "Default")
      (node (ref "U9") (pin "4") (pinfunction "NC_4") (pintype "passive+no_connect"))
    )
  )
)
